# mosfet-drv-for-draft.net
KiCad netlist of a schematic drawn in EAGLE
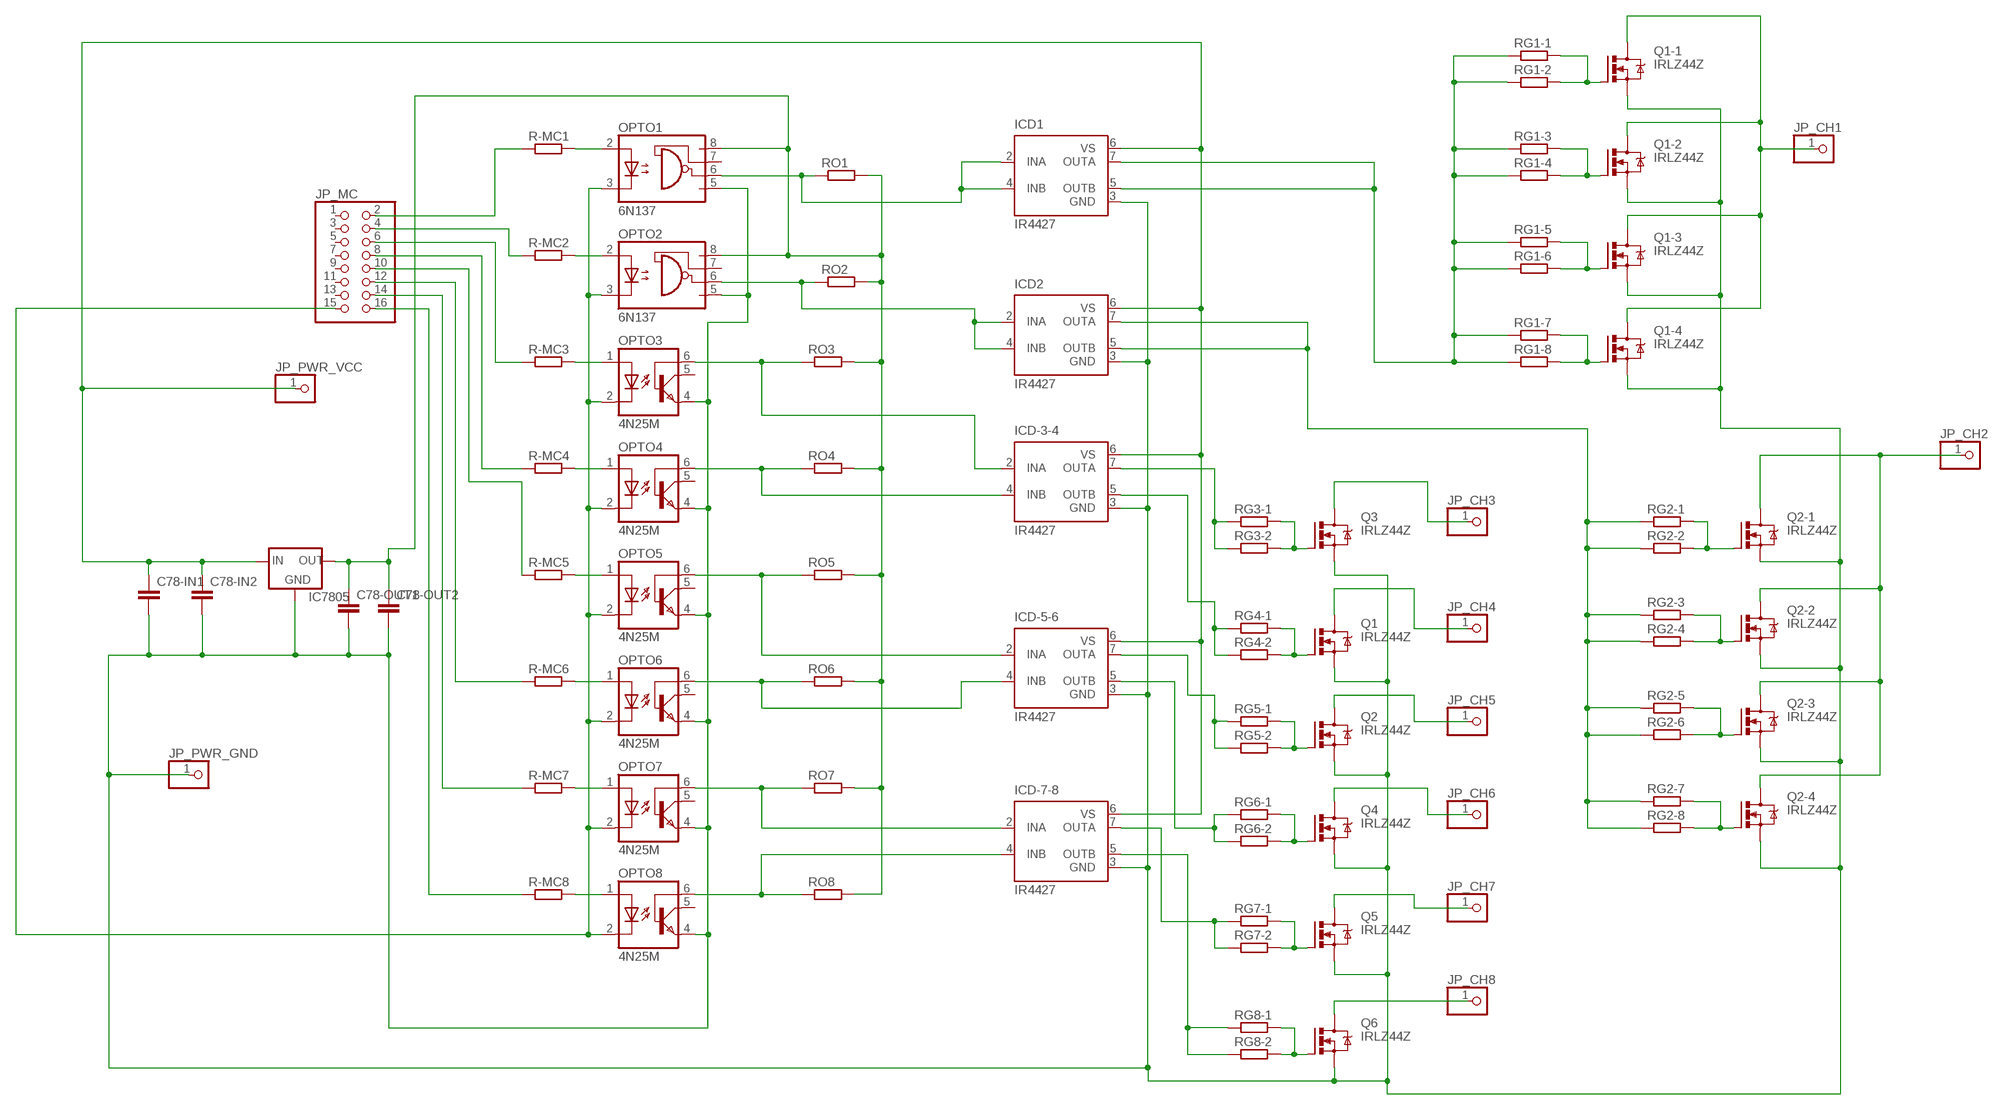
[diagram p0: schematic, sheet 1]

(export (version "E")
  (design (tool "Eeschema 10.0.6"))
  (components
    (comp (ref "C78-IN1")
      (value "C-EU025-060X050")
      (footprint "eagle-import:C025-060X050")
      (libsource (lib "eagle-import") (part "C-EU025-060X050"))
    )
    (comp (ref "C78-IN2")
      (value "C-EU025-060X050")
      (footprint "eagle-import:C025-060X050")
      (libsource (lib "eagle-import") (part "C-EU025-060X050"))
    )
    (comp (ref "C78-OUT1")
      (value "C-EU025-060X050")
      (footprint "eagle-import:C025-060X050")
      (libsource (lib "eagle-import") (part "C-EU025-060X050"))
    )
    (comp (ref "C78-OUT2")
      (value "C-EU025-060X050")
      (footprint "eagle-import:C025-060X050")
      (libsource (lib "eagle-import") (part "C-EU025-060X050"))
    )
    (comp (ref "IC7805")
      (value "78XXS")
      (footprint "eagle-import:78XXS")
      (libsource (lib "eagle-import") (part "78XXS"))
    )
    (comp (ref "ICD-3-4")
      (value "IR4427")
      (footprint "eagle-import:DIL08")
      (fields (field (name "MF") "INTERNATIONAL RECTIFIER(IR)"))
      (libsource (lib "eagle-import") (part "IR4427"))
    )
    (comp (ref "ICD-5-6")
      (value "IR4427")
      (footprint "eagle-import:DIL08")
      (fields (field (name "MF") "INTERNATIONAL RECTIFIER(IR)"))
      (libsource (lib "eagle-import") (part "IR4427"))
    )
    (comp (ref "ICD-7-8")
      (value "IR4427")
      (footprint "eagle-import:DIL08")
      (fields (field (name "MF") "INTERNATIONAL RECTIFIER(IR)"))
      (libsource (lib "eagle-import") (part "IR4427"))
    )
    (comp (ref "ICD1")
      (value "IR4427")
      (footprint "eagle-import:DIL08")
      (fields (field (name "MF") "INTERNATIONAL RECTIFIER(IR)"))
      (libsource (lib "eagle-import") (part "IR4427"))
    )
    (comp (ref "ICD2")
      (value "IR4427")
      (footprint "eagle-import:DIL08")
      (fields (field (name "MF") "INTERNATIONAL RECTIFIER(IR)"))
      (libsource (lib "eagle-import") (part "IR4427"))
    )
    (comp (ref "JP_CH1")
      (value "PINHD-1X1")
      (footprint "eagle-import:1X01")
      (libsource (lib "eagle-import") (part "PINHD-1X1"))
    )
    (comp (ref "JP_CH2")
      (value "PINHD-1X1")
      (footprint "eagle-import:1X01")
      (libsource (lib "eagle-import") (part "PINHD-1X1"))
    )
    (comp (ref "JP_CH3")
      (value "PINHD-1X1")
      (footprint "eagle-import:1X01")
      (libsource (lib "eagle-import") (part "PINHD-1X1"))
    )
    (comp (ref "JP_CH4")
      (value "PINHD-1X1")
      (footprint "eagle-import:1X01")
      (libsource (lib "eagle-import") (part "PINHD-1X1"))
    )
    (comp (ref "JP_CH5")
      (value "PINHD-1X1")
      (footprint "eagle-import:1X01")
      (libsource (lib "eagle-import") (part "PINHD-1X1"))
    )
    (comp (ref "JP_CH6")
      (value "PINHD-1X1")
      (footprint "eagle-import:1X01")
      (libsource (lib "eagle-import") (part "PINHD-1X1"))
    )
    (comp (ref "JP_CH7")
      (value "PINHD-1X1")
      (footprint "eagle-import:1X01")
      (libsource (lib "eagle-import") (part "PINHD-1X1"))
    )
    (comp (ref "JP_CH8")
      (value "PINHD-1X1")
      (footprint "eagle-import:1X01")
      (libsource (lib "eagle-import") (part "PINHD-1X1"))
    )
    (comp (ref "JP_MC")
      (value "PINHD-2X8")
      (footprint "eagle-import:2X08")
      (libsource (lib "eagle-import") (part "PINHD-2X8"))
    )
    (comp (ref "JP_PWR_GND")
      (value "PINHD-1X1")
      (footprint "eagle-import:1X01")
      (libsource (lib "eagle-import") (part "PINHD-1X1"))
    )
    (comp (ref "JP_PWR_VCC")
      (value "PINHD-1X1")
      (footprint "eagle-import:1X01")
      (libsource (lib "eagle-import") (part "PINHD-1X1"))
    )
    (comp (ref "OPTO1")
      (value "6N137")
      (footprint "eagle-import:DIL08")
      (libsource (lib "eagle-import") (part "6N137"))
    )
    (comp (ref "OPTO2")
      (value "6N137")
      (footprint "eagle-import:DIL08")
      (libsource (lib "eagle-import") (part "6N137"))
    )
    (comp (ref "OPTO3")
      (value "4N25M")
      (footprint "eagle-import:DIL06")
      (fields (field (name "MPN") "4N25-M"))
      (libsource (lib "eagle-import") (part "4N?M25"))
    )
    (comp (ref "OPTO4")
      (value "4N25M")
      (footprint "eagle-import:DIL06")
      (fields (field (name "MPN") "4N25-M"))
      (libsource (lib "eagle-import") (part "4N?M25"))
    )
    (comp (ref "OPTO5")
      (value "4N25M")
      (footprint "eagle-import:DIL06")
      (fields (field (name "MPN") "4N25-M"))
      (libsource (lib "eagle-import") (part "4N?M25"))
    )
    (comp (ref "OPTO6")
      (value "4N25M")
      (footprint "eagle-import:DIL06")
      (fields (field (name "MPN") "4N25-M"))
      (libsource (lib "eagle-import") (part "4N?M25"))
    )
    (comp (ref "OPTO7")
      (value "4N25M")
      (footprint "eagle-import:DIL06")
      (fields (field (name "MPN") "4N25-M"))
      (libsource (lib "eagle-import") (part "4N?M25"))
    )
    (comp (ref "OPTO8")
      (value "4N25M")
      (footprint "eagle-import:DIL06")
      (fields (field (name "MPN") "4N25-M"))
      (libsource (lib "eagle-import") (part "4N?M25"))
    )
    (comp (ref "Q1")
      (value "IRLZ44Z")
      (footprint "eagle-import:TO220BH")
      (libsource (lib "eagle-import") (part "IRLZ44Z"))
    )
    (comp (ref "Q1-1")
      (value "IRLZ44Z")
      (footprint "eagle-import:TO220BH")
      (libsource (lib "eagle-import") (part "IRLZ44Z"))
    )
    (comp (ref "Q1-2")
      (value "IRLZ44Z")
      (footprint "eagle-import:TO220BH")
      (libsource (lib "eagle-import") (part "IRLZ44Z"))
    )
    (comp (ref "Q1-3")
      (value "IRLZ44Z")
      (footprint "eagle-import:TO220BH")
      (libsource (lib "eagle-import") (part "IRLZ44Z"))
    )
    (comp (ref "Q1-4")
      (value "IRLZ44Z")
      (footprint "eagle-import:TO220BH")
      (libsource (lib "eagle-import") (part "IRLZ44Z"))
    )
    (comp (ref "Q2")
      (value "IRLZ44Z")
      (footprint "eagle-import:TO220BH")
      (libsource (lib "eagle-import") (part "IRLZ44Z"))
    )
    (comp (ref "Q2-1")
      (value "IRLZ44Z")
      (footprint "eagle-import:TO220BH")
      (libsource (lib "eagle-import") (part "IRLZ44Z"))
    )
    (comp (ref "Q2-2")
      (value "IRLZ44Z")
      (footprint "eagle-import:TO220BH")
      (libsource (lib "eagle-import") (part "IRLZ44Z"))
    )
    (comp (ref "Q2-3")
      (value "IRLZ44Z")
      (footprint "eagle-import:TO220BH")
      (libsource (lib "eagle-import") (part "IRLZ44Z"))
    )
    (comp (ref "Q2-4")
      (value "IRLZ44Z")
      (footprint "eagle-import:TO220BH")
      (libsource (lib "eagle-import") (part "IRLZ44Z"))
    )
    (comp (ref "Q3")
      (value "IRLZ44Z")
      (footprint "eagle-import:TO220BH")
      (libsource (lib "eagle-import") (part "IRLZ44Z"))
    )
    (comp (ref "Q4")
      (value "IRLZ44Z")
      (footprint "eagle-import:TO220BH")
      (libsource (lib "eagle-import") (part "IRLZ44Z"))
    )
    (comp (ref "Q5")
      (value "IRLZ44Z")
      (footprint "eagle-import:TO220BH")
      (libsource (lib "eagle-import") (part "IRLZ44Z"))
    )
    (comp (ref "Q6")
      (value "IRLZ44Z")
      (footprint "eagle-import:TO220BH")
      (libsource (lib "eagle-import") (part "IRLZ44Z"))
    )
    (comp (ref "R-MC1")
      (value "R-EU_M1206")
      (footprint "eagle-import:M1206")
      (libsource (lib "eagle-import") (part "R-EU_M1206"))
    )
    (comp (ref "R-MC2")
      (value "R-EU_M1206")
      (footprint "eagle-import:M1206")
      (libsource (lib "eagle-import") (part "R-EU_M1206"))
    )
    (comp (ref "R-MC3")
      (value "R-EU_M1206")
      (footprint "eagle-import:M1206")
      (libsource (lib "eagle-import") (part "R-EU_M1206"))
    )
    (comp (ref "R-MC4")
      (value "R-EU_M1206")
      (footprint "eagle-import:M1206")
      (libsource (lib "eagle-import") (part "R-EU_M1206"))
    )
    (comp (ref "R-MC5")
      (value "R-EU_M1206")
      (footprint "eagle-import:M1206")
      (libsource (lib "eagle-import") (part "R-EU_M1206"))
    )
    (comp (ref "R-MC6")
      (value "R-EU_M1206")
      (footprint "eagle-import:M1206")
      (libsource (lib "eagle-import") (part "R-EU_M1206"))
    )
    (comp (ref "R-MC7")
      (value "R-EU_M1206")
      (footprint "eagle-import:M1206")
      (libsource (lib "eagle-import") (part "R-EU_M1206"))
    )
    (comp (ref "R-MC8")
      (value "R-EU_M1206")
      (footprint "eagle-import:M1206")
      (libsource (lib "eagle-import") (part "R-EU_M1206"))
    )
    (comp (ref "RG1-1")
      (value "R-EU_0207/15")
      (footprint "eagle-import:0207_15")
      (libsource (lib "eagle-import") (part "R-EU_0207/15"))
    )
    (comp (ref "RG1-2")
      (value "R-EU_0207/15")
      (footprint "eagle-import:0207_15")
      (libsource (lib "eagle-import") (part "R-EU_0207/15"))
    )
    (comp (ref "RG1-3")
      (value "R-EU_0207/15")
      (footprint "eagle-import:0207_15")
      (libsource (lib "eagle-import") (part "R-EU_0207/15"))
    )
    (comp (ref "RG1-4")
      (value "R-EU_0207/15")
      (footprint "eagle-import:0207_15")
      (libsource (lib "eagle-import") (part "R-EU_0207/15"))
    )
    (comp (ref "RG1-5")
      (value "R-EU_0207/15")
      (footprint "eagle-import:0207_15")
      (libsource (lib "eagle-import") (part "R-EU_0207/15"))
    )
    (comp (ref "RG1-6")
      (value "R-EU_0207/15")
      (footprint "eagle-import:0207_15")
      (libsource (lib "eagle-import") (part "R-EU_0207/15"))
    )
    (comp (ref "RG1-7")
      (value "R-EU_0207/15")
      (footprint "eagle-import:0207_15")
      (libsource (lib "eagle-import") (part "R-EU_0207/15"))
    )
    (comp (ref "RG1-8")
      (value "R-EU_0207/15")
      (footprint "eagle-import:0207_15")
      (libsource (lib "eagle-import") (part "R-EU_0207/15"))
    )
    (comp (ref "RG2-1")
      (value "R-EU_0207/15")
      (footprint "eagle-import:0207_15")
      (libsource (lib "eagle-import") (part "R-EU_0207/15"))
    )
    (comp (ref "RG2-2")
      (value "R-EU_0207/15")
      (footprint "eagle-import:0207_15")
      (libsource (lib "eagle-import") (part "R-EU_0207/15"))
    )
    (comp (ref "RG2-3")
      (value "R-EU_0207/15")
      (footprint "eagle-import:0207_15")
      (libsource (lib "eagle-import") (part "R-EU_0207/15"))
    )
    (comp (ref "RG2-4")
      (value "R-EU_0207/15")
      (footprint "eagle-import:0207_15")
      (libsource (lib "eagle-import") (part "R-EU_0207/15"))
    )
    (comp (ref "RG2-5")
      (value "R-EU_0207/15")
      (footprint "eagle-import:0207_15")
      (libsource (lib "eagle-import") (part "R-EU_0207/15"))
    )
    (comp (ref "RG2-6")
      (value "R-EU_0207/15")
      (footprint "eagle-import:0207_15")
      (libsource (lib "eagle-import") (part "R-EU_0207/15"))
    )
    (comp (ref "RG2-7")
      (value "R-EU_0207/15")
      (footprint "eagle-import:0207_15")
      (libsource (lib "eagle-import") (part "R-EU_0207/15"))
    )
    (comp (ref "RG2-8")
      (value "R-EU_0207/15")
      (footprint "eagle-import:0207_15")
      (libsource (lib "eagle-import") (part "R-EU_0207/15"))
    )
    (comp (ref "RG3-1")
      (value "R-EU_0207/15")
      (footprint "eagle-import:0207_15")
      (libsource (lib "eagle-import") (part "R-EU_0207/15"))
    )
    (comp (ref "RG3-2")
      (value "R-EU_0207/15")
      (footprint "eagle-import:0207_15")
      (libsource (lib "eagle-import") (part "R-EU_0207/15"))
    )
    (comp (ref "RG4-1")
      (value "R-EU_0207/15")
      (footprint "eagle-import:0207_15")
      (libsource (lib "eagle-import") (part "R-EU_0207/15"))
    )
    (comp (ref "RG4-2")
      (value "R-EU_0207/15")
      (footprint "eagle-import:0207_15")
      (libsource (lib "eagle-import") (part "R-EU_0207/15"))
    )
    (comp (ref "RG5-1")
      (value "R-EU_0207/15")
      (footprint "eagle-import:0207_15")
      (libsource (lib "eagle-import") (part "R-EU_0207/15"))
    )
    (comp (ref "RG5-2")
      (value "R-EU_0207/15")
      (footprint "eagle-import:0207_15")
      (libsource (lib "eagle-import") (part "R-EU_0207/15"))
    )
    (comp (ref "RG6-1")
      (value "R-EU_0207/15")
      (footprint "eagle-import:0207_15")
      (libsource (lib "eagle-import") (part "R-EU_0207/15"))
    )
    (comp (ref "RG6-2")
      (value "R-EU_0207/15")
      (footprint "eagle-import:0207_15")
      (libsource (lib "eagle-import") (part "R-EU_0207/15"))
    )
    (comp (ref "RG7-1")
      (value "R-EU_0207/15")
      (footprint "eagle-import:0207_15")
      (libsource (lib "eagle-import") (part "R-EU_0207/15"))
    )
    (comp (ref "RG7-2")
      (value "R-EU_0207/15")
      (footprint "eagle-import:0207_15")
      (libsource (lib "eagle-import") (part "R-EU_0207/15"))
    )
    (comp (ref "RG8-1")
      (value "R-EU_0207/15")
      (footprint "eagle-import:0207_15")
      (libsource (lib "eagle-import") (part "R-EU_0207/15"))
    )
    (comp (ref "RG8-2")
      (value "R-EU_0207/15")
      (footprint "eagle-import:0207_15")
      (libsource (lib "eagle-import") (part "R-EU_0207/15"))
    )
    (comp (ref "RO1")
      (value "R-EU_M1206")
      (footprint "eagle-import:M1206")
      (libsource (lib "eagle-import") (part "R-EU_M1206"))
    )
    (comp (ref "RO2")
      (value "R-EU_M1206")
      (footprint "eagle-import:M1206")
      (libsource (lib "eagle-import") (part "R-EU_M1206"))
    )
    (comp (ref "RO3")
      (value "R-EU_M1206")
      (footprint "eagle-import:M1206")
      (libsource (lib "eagle-import") (part "R-EU_M1206"))
    )
    (comp (ref "RO4")
      (value "R-EU_M1206")
      (footprint "eagle-import:M1206")
      (libsource (lib "eagle-import") (part "R-EU_M1206"))
    )
    (comp (ref "RO5")
      (value "R-EU_M1206")
      (footprint "eagle-import:M1206")
      (libsource (lib "eagle-import") (part "R-EU_M1206"))
    )
    (comp (ref "RO6")
      (value "R-EU_M1206")
      (footprint "eagle-import:M1206")
      (libsource (lib "eagle-import") (part "R-EU_M1206"))
    )
    (comp (ref "RO7")
      (value "R-EU_M1206")
      (footprint "eagle-import:M1206")
      (libsource (lib "eagle-import") (part "R-EU_M1206"))
    )
    (comp (ref "RO8")
      (value "R-EU_M1206")
      (footprint "eagle-import:M1206")
      (libsource (lib "eagle-import") (part "R-EU_M1206"))
    )
  )
  (nets
    (net (code "1") (name "Net-(ICD-3-4-GND)") (class "Default")
      (node (ref "C78-IN1") (pin "2") (pinfunction "2_2") (pintype "passive"))
      (node (ref "C78-IN2") (pin "2") (pinfunction "2_2") (pintype "passive"))
      (node (ref "C78-OUT1") (pin "2") (pinfunction "2_2") (pintype "passive"))
      (node (ref "C78-OUT2") (pin "2") (pinfunction "2_2") (pintype "passive"))
      (node (ref "IC7805") (pin "GND") (pinfunction "GND_GND") (pintype "input"))
      (node (ref "ICD-3-4") (pin "3") (pinfunction "GND_3") (pintype "power_in"))
      (node (ref "ICD-5-6") (pin "3") (pinfunction "GND_3") (pintype "power_in"))
      (node (ref "ICD-7-8") (pin "3") (pinfunction "GND_3") (pintype "power_in"))
      (node (ref "ICD1") (pin "3") (pinfunction "GND_3") (pintype "power_in"))
      (node (ref "ICD2") (pin "3") (pinfunction "GND_3") (pintype "power_in"))
      (node (ref "JP_PWR_GND") (pin "1") (pinfunction "1_1") (pintype "passive"))
      (node (ref "OPTO1") (pin "5") (pinfunction "GND_5") (pintype "passive"))
      (node (ref "OPTO2") (pin "5") (pinfunction "GND_5") (pintype "passive"))
      (node (ref "OPTO3") (pin "4") (pinfunction "EMI_4") (pintype "passive"))
      (node (ref "OPTO4") (pin "4") (pinfunction "EMI_4") (pintype "passive"))
      (node (ref "OPTO5") (pin "4") (pinfunction "EMI_4") (pintype "passive"))
      (node (ref "OPTO6") (pin "4") (pinfunction "EMI_4") (pintype "passive"))
      (node (ref "OPTO7") (pin "4") (pinfunction "EMI_4") (pintype "passive"))
      (node (ref "OPTO8") (pin "4") (pinfunction "EMI_4") (pintype "passive"))
      (node (ref "Q1") (pin "S") (pinfunction "S_S") (pintype "passive"))
      (node (ref "Q1-1") (pin "S") (pinfunction "S_S") (pintype "passive"))
      (node (ref "Q1-2") (pin "S") (pinfunction "S_S") (pintype "passive"))
      (node (ref "Q1-3") (pin "S") (pinfunction "S_S") (pintype "passive"))
      (node (ref "Q1-4") (pin "S") (pinfunction "S_S") (pintype "passive"))
      (node (ref "Q2") (pin "S") (pinfunction "S_S") (pintype "passive"))
      (node (ref "Q2-1") (pin "S") (pinfunction "S_S") (pintype "passive"))
      (node (ref "Q2-2") (pin "S") (pinfunction "S_S") (pintype "passive"))
      (node (ref "Q2-3") (pin "S") (pinfunction "S_S") (pintype "passive"))
      (node (ref "Q2-4") (pin "S") (pinfunction "S_S") (pintype "passive"))
      (node (ref "Q3") (pin "S") (pinfunction "S_S") (pintype "passive"))
      (node (ref "Q4") (pin "S") (pinfunction "S_S") (pintype "passive"))
      (node (ref "Q5") (pin "S") (pinfunction "S_S") (pintype "passive"))
      (node (ref "Q6") (pin "S") (pinfunction "S_S") (pintype "passive"))
    )
    (net (code "2") (name "Net-(ICD-3-4-INA)") (class "Default")
      (node (ref "ICD-3-4") (pin "2") (pinfunction "INA_2") (pintype "input"))
      (node (ref "OPTO3") (pin "6") (pinfunction "BAS_6") (pintype "passive"))
      (node (ref "RO3") (pin "1") (pinfunction "1_1") (pintype "passive"))
    )
    (net (code "3") (name "Net-(ICD-3-4-INB)") (class "Default")
      (node (ref "ICD-3-4") (pin "4") (pinfunction "INB_4") (pintype "input"))
      (node (ref "OPTO4") (pin "6") (pinfunction "BAS_6") (pintype "passive"))
      (node (ref "RO4") (pin "1") (pinfunction "1_1") (pintype "passive"))
    )
    (net (code "4") (name "Net-(ICD-3-4-OUTA)") (class "Default")
      (node (ref "ICD-3-4") (pin "7") (pinfunction "OUTA_7") (pintype "output"))
      (node (ref "RG3-1") (pin "1") (pinfunction "1_1") (pintype "passive"))
      (node (ref "RG3-2") (pin "1") (pinfunction "1_1") (pintype "passive"))
    )
    (net (code "5") (name "Net-(ICD-3-4-OUTB)") (class "Default")
      (node (ref "ICD-3-4") (pin "5") (pinfunction "OUTB_5") (pintype "output"))
      (node (ref "RG4-1") (pin "1") (pinfunction "1_1") (pintype "passive"))
      (node (ref "RG4-2") (pin "1") (pinfunction "1_1") (pintype "passive"))
    )
    (net (code "6") (name "Net-(ICD-3-4-VS)") (class "Default")
      (node (ref "C78-IN1") (pin "1") (pinfunction "1_1") (pintype "passive"))
      (node (ref "C78-IN2") (pin "1") (pinfunction "1_1") (pintype "passive"))
      (node (ref "IC7805") (pin "IN") (pinfunction "IN_IN") (pintype "input"))
      (node (ref "ICD-3-4") (pin "6") (pinfunction "VS_6") (pintype "power_in"))
      (node (ref "ICD-5-6") (pin "6") (pinfunction "VS_6") (pintype "power_in"))
      (node (ref "ICD-7-8") (pin "6") (pinfunction "VS_6") (pintype "power_in"))
      (node (ref "ICD1") (pin "6") (pinfunction "VS_6") (pintype "power_in"))
      (node (ref "ICD2") (pin "6") (pinfunction "VS_6") (pintype "power_in"))
      (node (ref "JP_PWR_VCC") (pin "1") (pinfunction "1_1") (pintype "passive"))
    )
    (net (code "7") (name "Net-(ICD-5-6-INA)") (class "Default")
      (node (ref "ICD-5-6") (pin "2") (pinfunction "INA_2") (pintype "input"))
      (node (ref "OPTO5") (pin "6") (pinfunction "BAS_6") (pintype "passive"))
      (node (ref "RO5") (pin "1") (pinfunction "1_1") (pintype "passive"))
    )
    (net (code "8") (name "Net-(ICD-5-6-INB)") (class "Default")
      (node (ref "ICD-5-6") (pin "4") (pinfunction "INB_4") (pintype "input"))
      (node (ref "OPTO6") (pin "6") (pinfunction "BAS_6") (pintype "passive"))
      (node (ref "RO6") (pin "1") (pinfunction "1_1") (pintype "passive"))
    )
    (net (code "9") (name "Net-(ICD-5-6-OUTA)") (class "Default")
      (node (ref "ICD-5-6") (pin "7") (pinfunction "OUTA_7") (pintype "output"))
      (node (ref "RG5-1") (pin "1") (pinfunction "1_1") (pintype "passive"))
      (node (ref "RG5-2") (pin "1") (pinfunction "1_1") (pintype "passive"))
    )
    (net (code "10") (name "Net-(ICD-5-6-OUTB)") (class "Default")
      (node (ref "ICD-5-6") (pin "5") (pinfunction "OUTB_5") (pintype "output"))
      (node (ref "RG6-1") (pin "1") (pinfunction "1_1") (pintype "passive"))
      (node (ref "RG6-2") (pin "1") (pinfunction "1_1") (pintype "passive"))
    )
    (net (code "11") (name "Net-(ICD-7-8-INA)") (class "Default")
      (node (ref "ICD-7-8") (pin "2") (pinfunction "INA_2") (pintype "input"))
      (node (ref "OPTO7") (pin "6") (pinfunction "BAS_6") (pintype "passive"))
      (node (ref "RO7") (pin "1") (pinfunction "1_1") (pintype "passive"))
    )
    (net (code "12") (name "Net-(ICD-7-8-INB)") (class "Default")
      (node (ref "ICD-7-8") (pin "4") (pinfunction "INB_4") (pintype "input"))
      (node (ref "OPTO8") (pin "6") (pinfunction "BAS_6") (pintype "passive"))
      (node (ref "RO8") (pin "1") (pinfunction "1_1") (pintype "passive"))
    )
    (net (code "13") (name "Net-(ICD-7-8-OUTA)") (class "Default")
      (node (ref "ICD-7-8") (pin "7") (pinfunction "OUTA_7") (pintype "output"))
      (node (ref "RG7-1") (pin "1") (pinfunction "1_1") (pintype "passive"))
      (node (ref "RG7-2") (pin "1") (pinfunction "1_1") (pintype "passive"))
    )
    (net (code "14") (name "Net-(ICD-7-8-OUTB)") (class "Default")
      (node (ref "ICD-7-8") (pin "5") (pinfunction "OUTB_5") (pintype "output"))
      (node (ref "RG8-1") (pin "1") (pinfunction "1_1") (pintype "passive"))
      (node (ref "RG8-2") (pin "1") (pinfunction "1_1") (pintype "passive"))
    )
    (net (code "15") (name "Net-(ICD1-INA)") (class "Default")
      (node (ref "ICD1") (pin "2") (pinfunction "INA_2") (pintype "input"))
      (node (ref "ICD1") (pin "4") (pinfunction "INB_4") (pintype "input"))
      (node (ref "OPTO1") (pin "6") (pinfunction "VO_6") (pintype "passive"))
      (node (ref "RO1") (pin "1") (pinfunction "1_1") (pintype "passive"))
    )
    (net (code "16") (name "Net-(ICD1-OUTA)") (class "Default")
      (node (ref "ICD1") (pin "5") (pinfunction "OUTB_5") (pintype "output"))
      (node (ref "ICD1") (pin "7") (pinfunction "OUTA_7") (pintype "output"))
      (node (ref "RG1-1") (pin "1") (pinfunction "1_1") (pintype "passive"))
      (node (ref "RG1-2") (pin "1") (pinfunction "1_1") (pintype "passive"))
      (node (ref "RG1-3") (pin "1") (pinfunction "1_1") (pintype "passive"))
      (node (ref "RG1-4") (pin "1") (pinfunction "1_1") (pintype "passive"))
      (node (ref "RG1-5") (pin "1") (pinfunction "1_1") (pintype "passive"))
      (node (ref "RG1-6") (pin "1") (pinfunction "1_1") (pintype "passive"))
      (node (ref "RG1-7") (pin "1") (pinfunction "1_1") (pintype "passive"))
      (node (ref "RG1-8") (pin "1") (pinfunction "1_1") (pintype "passive"))
    )
    (net (code "17") (name "Net-(ICD2-INA)") (class "Default")
      (node (ref "ICD2") (pin "2") (pinfunction "INA_2") (pintype "input"))
      (node (ref "ICD2") (pin "4") (pinfunction "INB_4") (pintype "input"))
      (node (ref "OPTO2") (pin "6") (pinfunction "VO_6") (pintype "passive"))
      (node (ref "RO2") (pin "1") (pinfunction "1_1") (pintype "passive"))
    )
    (net (code "18") (name "Net-(ICD2-OUTA)") (class "Default")
      (node (ref "ICD2") (pin "5") (pinfunction "OUTB_5") (pintype "output"))
      (node (ref "ICD2") (pin "7") (pinfunction "OUTA_7") (pintype "output"))
      (node (ref "RG2-1") (pin "1") (pinfunction "1_1") (pintype "passive"))
      (node (ref "RG2-2") (pin "1") (pinfunction "1_1") (pintype "passive"))
      (node (ref "RG2-3") (pin "1") (pinfunction "1_1") (pintype "passive"))
      (node (ref "RG2-4") (pin "1") (pinfunction "1_1") (pintype "passive"))
      (node (ref "RG2-5") (pin "1") (pinfunction "1_1") (pintype "passive"))
      (node (ref "RG2-6") (pin "1") (pinfunction "1_1") (pintype "passive"))
      (node (ref "RG2-7") (pin "1") (pinfunction "1_1") (pintype "passive"))
      (node (ref "RG2-8") (pin "1") (pinfunction "1_1") (pintype "passive"))
    )
    (net (code "19") (name "Net-(JP_CH1-Pad1)") (class "Default")
      (node (ref "JP_CH1") (pin "1") (pinfunction "1_1") (pintype "passive"))
      (node (ref "Q1-1") (pin "D") (pinfunction "D_D") (pintype "passive"))
      (node (ref "Q1-2") (pin "D") (pinfunction "D_D") (pintype "passive"))
      (node (ref "Q1-3") (pin "D") (pinfunction "D_D") (pintype "passive"))
      (node (ref "Q1-4") (pin "D") (pinfunction "D_D") (pintype "passive"))
    )
    (net (code "20") (name "Net-(JP_CH2-Pad1)") (class "Default")
      (node (ref "JP_CH2") (pin "1") (pinfunction "1_1") (pintype "passive"))
      (node (ref "Q2-1") (pin "D") (pinfunction "D_D") (pintype "passive"))
      (node (ref "Q2-2") (pin "D") (pinfunction "D_D") (pintype "passive"))
      (node (ref "Q2-3") (pin "D") (pinfunction "D_D") (pintype "passive"))
      (node (ref "Q2-4") (pin "D") (pinfunction "D_D") (pintype "passive"))
    )
    (net (code "21") (name "Net-(JP_CH3-Pad1)") (class "Default")
      (node (ref "JP_CH3") (pin "1") (pinfunction "1_1") (pintype "passive"))
      (node (ref "Q3") (pin "D") (pinfunction "D_D") (pintype "passive"))
    )
    (net (code "22") (name "Net-(JP_CH4-Pad1)") (class "Default")
      (node (ref "JP_CH4") (pin "1") (pinfunction "1_1") (pintype "passive"))
      (node (ref "Q1") (pin "D") (pinfunction "D_D") (pintype "passive"))
    )
    (net (code "23") (name "Net-(JP_CH5-Pad1)") (class "Default")
      (node (ref "JP_CH5") (pin "1") (pinfunction "1_1") (pintype "passive"))
      (node (ref "Q2") (pin "D") (pinfunction "D_D") (pintype "passive"))
    )
    (net (code "24") (name "Net-(JP_CH6-Pad1)") (class "Default")
      (node (ref "JP_CH6") (pin "1") (pinfunction "1_1") (pintype "passive"))
      (node (ref "Q4") (pin "D") (pinfunction "D_D") (pintype "passive"))
    )
    (net (code "25") (name "Net-(JP_CH7-Pad1)") (class "Default")
      (node (ref "JP_CH7") (pin "1") (pinfunction "1_1") (pintype "passive"))
      (node (ref "Q5") (pin "D") (pinfunction "D_D") (pintype "passive"))
    )
    (net (code "26") (name "Net-(JP_CH8-Pad1)") (class "Default")
      (node (ref "JP_CH8") (pin "1") (pinfunction "1_1") (pintype "passive"))
      (node (ref "Q6") (pin "D") (pinfunction "D_D") (pintype "passive"))
    )
    (net (code "27") (name "Net-(JP_MC-Pad2)") (class "Default")
      (node (ref "JP_MC") (pin "2") (pinfunction "2_2") (pintype "passive"))
      (node (ref "R-MC1") (pin "1") (pinfunction "1_1") (pintype "passive"))
    )
    (net (code "28") (name "Net-(JP_MC-Pad4)") (class "Default")
      (node (ref "JP_MC") (pin "4") (pinfunction "4_4") (pintype "passive"))
      (node (ref "R-MC2") (pin "1") (pinfunction "1_1") (pintype "passive"))
    )
    (net (code "29") (name "Net-(JP_MC-Pad6)") (class "Default")
      (node (ref "JP_MC") (pin "6") (pinfunction "6_6") (pintype "passive"))
      (node (ref "R-MC3") (pin "1") (pinfunction "1_1") (pintype "passive"))
    )
    (net (code "30") (name "Net-(JP_MC-Pad8)") (class "Default")
      (node (ref "JP_MC") (pin "8") (pinfunction "8_8") (pintype "passive"))
      (node (ref "R-MC4") (pin "1") (pinfunction "1_1") (pintype "passive"))
    )
    (net (code "31") (name "Net-(JP_MC-Pad10)") (class "Default")
      (node (ref "JP_MC") (pin "10") (pinfunction "10_10") (pintype "passive"))
      (node (ref "R-MC5") (pin "1") (pinfunction "1_1") (pintype "passive"))
    )
    (net (code "32") (name "Net-(JP_MC-Pad12)") (class "Default")
      (node (ref "JP_MC") (pin "12") (pinfunction "12_12") (pintype "passive"))
      (node (ref "R-MC6") (pin "1") (pinfunction "1_1") (pintype "passive"))
    )
    (net (code "33") (name "Net-(JP_MC-Pad14)") (class "Default")
      (node (ref "JP_MC") (pin "14") (pinfunction "14_14") (pintype "passive"))
      (node (ref "R-MC7") (pin "1") (pinfunction "1_1") (pintype "passive"))
    )
    (net (code "34") (name "Net-(JP_MC-Pad16)") (class "Default")
      (node (ref "JP_MC") (pin "16") (pinfunction "16_16") (pintype "passive"))
      (node (ref "R-MC8") (pin "1") (pinfunction "1_1") (pintype "passive"))
    )
    (net (code "35") (name "Net-(OPTO1-A)") (class "Default")
      (node (ref "OPTO1") (pin "2") (pinfunction "A_2") (pintype "passive"))
      (node (ref "R-MC1") (pin "2") (pinfunction "2_2") (pintype "passive"))
    )
    (net (code "36") (name "Net-(OPTO1-C)") (class "Default")
      (node (ref "JP_MC") (pin "15") (pinfunction "15_15") (pintype "passive"))
      (node (ref "OPTO1") (pin "3") (pinfunction "C_3") (pintype "passive"))
      (node (ref "OPTO2") (pin "3") (pinfunction "C_3") (pintype "passive"))
      (node (ref "OPTO3") (pin "2") (pinfunction "C_2") (pintype "passive"))
      (node (ref "OPTO4") (pin "2") (pinfunction "C_2") (pintype "passive"))
      (node (ref "OPTO5") (pin "2") (pinfunction "C_2") (pintype "passive"))
      (node (ref "OPTO6") (pin "2") (pinfunction "C_2") (pintype "passive"))
      (node (ref "OPTO7") (pin "2") (pinfunction "C_2") (pintype "passive"))
      (node (ref "OPTO8") (pin "2") (pinfunction "C_2") (pintype "passive"))
    )
    (net (code "37") (name "Net-(OPTO1-VCC)") (class "Default")
      (node (ref "C78-OUT1") (pin "1") (pinfunction "1_1") (pintype "passive"))
      (node (ref "C78-OUT2") (pin "1") (pinfunction "1_1") (pintype "passive"))
      (node (ref "IC7805") (pin "OUT") (pinfunction "OUT_OUT") (pintype "passive"))
      (node (ref "OPTO1") (pin "8") (pinfunction "VCC_8") (pintype "passive"))
      (node (ref "OPTO2") (pin "8") (pinfunction "VCC_8") (pintype "passive"))
      (node (ref "RO1") (pin "2") (pinfunction "2_2") (pintype "passive"))
      (node (ref "RO2") (pin "2") (pinfunction "2_2") (pintype "passive"))
      (node (ref "RO3") (pin "2") (pinfunction "2_2") (pintype "passive"))
      (node (ref "RO4") (pin "2") (pinfunction "2_2") (pintype "passive"))
      (node (ref "RO5") (pin "2") (pinfunction "2_2") (pintype "passive"))
      (node (ref "RO6") (pin "2") (pinfunction "2_2") (pintype "passive"))
      (node (ref "RO7") (pin "2") (pinfunction "2_2") (pintype "passive"))
      (node (ref "RO8") (pin "2") (pinfunction "2_2") (pintype "passive"))
    )
    (net (code "38") (name "Net-(OPTO2-A)") (class "Default")
      (node (ref "OPTO2") (pin "2") (pinfunction "A_2") (pintype "passive"))
      (node (ref "R-MC2") (pin "2") (pinfunction "2_2") (pintype "passive"))
    )
    (net (code "39") (name "Net-(OPTO3-A)") (class "Default")
      (node (ref "OPTO3") (pin "1") (pinfunction "A_1") (pintype "passive"))
      (node (ref "R-MC3") (pin "2") (pinfunction "2_2") (pintype "passive"))
    )
    (net (code "40") (name "Net-(OPTO4-A)") (class "Default")
      (node (ref "OPTO4") (pin "1") (pinfunction "A_1") (pintype "passive"))
      (node (ref "R-MC4") (pin "2") (pinfunction "2_2") (pintype "passive"))
    )
    (net (code "41") (name "Net-(OPTO5-A)") (class "Default")
      (node (ref "OPTO5") (pin "1") (pinfunction "A_1") (pintype "passive"))
      (node (ref "R-MC5") (pin "2") (pinfunction "2_2") (pintype "passive"))
    )
    (net (code "42") (name "Net-(OPTO6-A)") (class "Default")
      (node (ref "OPTO6") (pin "1") (pinfunction "A_1") (pintype "passive"))
      (node (ref "R-MC6") (pin "2") (pinfunction "2_2") (pintype "passive"))
    )
    (net (code "43") (name "Net-(OPTO7-A)") (class "Default")
      (node (ref "OPTO7") (pin "1") (pinfunction "A_1") (pintype "passive"))
      (node (ref "R-MC7") (pin "2") (pinfunction "2_2") (pintype "passive"))
    )
    (net (code "44") (name "Net-(OPTO8-A)") (class "Default")
      (node (ref "OPTO8") (pin "1") (pinfunction "A_1") (pintype "passive"))
      (node (ref "R-MC8") (pin "2") (pinfunction "2_2") (pintype "passive"))
    )
    (net (code "45") (name "Net-(Q1-1-PadG)") (class "Default")
      (node (ref "Q1-1") (pin "G") (pinfunction "G_G") (pintype "passive"))
      (node (ref "RG1-1") (pin "2") (pinfunction "2_2") (pintype "passive"))
      (node (ref "RG1-2") (pin "2") (pinfunction "2_2") (pintype "passive"))
    )
    (net (code "46") (name "Net-(Q1-2-PadG)") (class "Default")
      (node (ref "Q1-2") (pin "G") (pinfunction "G_G") (pintype "passive"))
      (node (ref "RG1-3") (pin "2") (pinfunction "2_2") (pintype "passive"))
      (node (ref "RG1-4") (pin "2") (pinfunction "2_2") (pintype "passive"))
    )
    (net (code "47") (name "Net-(Q1-3-PadG)") (class "Default")
      (node (ref "Q1-3") (pin "G") (pinfunction "G_G") (pintype "passive"))
      (node (ref "RG1-5") (pin "2") (pinfunction "2_2") (pintype "passive"))
      (node (ref "RG1-6") (pin "2") (pinfunction "2_2") (pintype "passive"))
    )
    (net (code "48") (name "Net-(Q1-4-PadG)") (class "Default")
      (node (ref "Q1-4") (pin "G") (pinfunction "G_G") (pintype "passive"))
      (node (ref "RG1-7") (pin "2") (pinfunction "2_2") (pintype "passive"))
      (node (ref "RG1-8") (pin "2") (pinfunction "2_2") (pintype "passive"))
    )
    (net (code "49") (name "Net-(Q1-PadG)") (class "Default")
      (node (ref "Q1") (pin "G") (pinfunction "G_G") (pintype "passive"))
      (node (ref "RG4-1") (pin "2") (pinfunction "2_2") (pintype "passive"))
      (node (ref "RG4-2") (pin "2") (pinfunction "2_2") (pintype "passive"))
    )
    (net (code "50") (name "Net-(Q2-1-PadG)") (class "Default")
      (node (ref "Q2-1") (pin "G") (pinfunction "G_G") (pintype "passive"))
      (node (ref "RG2-1") (pin "2") (pinfunction "2_2") (pintype "passive"))
      (node (ref "RG2-2") (pin "2") (pinfunction "2_2") (pintype "passive"))
    )
    (net (code "51") (name "Net-(Q2-2-PadG)") (class "Default")
      (node (ref "Q2-2") (pin "G") (pinfunction "G_G") (pintype "passive"))
      (node (ref "RG2-3") (pin "2") (pinfunction "2_2") (pintype "passive"))
      (node (ref "RG2-4") (pin "2") (pinfunction "2_2") (pintype "passive"))
    )
    (net (code "52") (name "Net-(Q2-3-PadG)") (class "Default")
      (node (ref "Q2-3") (pin "G") (pinfunction "G_G") (pintype "passive"))
      (node (ref "RG2-5") (pin "2") (pinfunction "2_2") (pintype "passive"))
      (node (ref "RG2-6") (pin "2") (pinfunction "2_2") (pintype "passive"))
    )
    (net (code "53") (name "Net-(Q2-4-PadG)") (class "Default")
      (node (ref "Q2-4") (pin "G") (pinfunction "G_G") (pintype "passive"))
      (node (ref "RG2-7") (pin "2") (pinfunction "2_2") (pintype "passive"))
      (node (ref "RG2-8") (pin "2") (pinfunction "2_2") (pintype "passive"))
    )
    (net (code "54") (name "Net-(Q2-PadG)") (class "Default")
      (node (ref "Q2") (pin "G") (pinfunction "G_G") (pintype "passive"))
      (node (ref "RG5-1") (pin "2") (pinfunction "2_2") (pintype "passive"))
      (node (ref "RG5-2") (pin "2") (pinfunction "2_2") (pintype "passive"))
    )
    (net (code "55") (name "Net-(Q3-PadG)") (class "Default")
      (node (ref "Q3") (pin "G") (pinfunction "G_G") (pintype "passive"))
      (node (ref "RG3-1") (pin "2") (pinfunction "2_2") (pintype "passive"))
      (node (ref "RG3-2") (pin "2") (pinfunction "2_2") (pintype "passive"))
    )
    (net (code "56") (name "Net-(Q4-PadG)") (class "Default")
      (node (ref "Q4") (pin "G") (pinfunction "G_G") (pintype "passive"))
      (node (ref "RG6-1") (pin "2") (pinfunction "2_2") (pintype "passive"))
      (node (ref "RG6-2") (pin "2") (pinfunction "2_2") (pintype "passive"))
    )
    (net (code "57") (name "Net-(Q5-PadG)") (class "Default")
      (node (ref "Q5") (pin "G") (pinfunction "G_G") (pintype "passive"))
      (node (ref "RG7-1") (pin "2") (pinfunction "2_2") (pintype "passive"))
      (node (ref "RG7-2") (pin "2") (pinfunction "2_2") (pintype "passive"))
    )
    (net (code "58") (name "Net-(Q6-PadG)") (class "Default")
      (node (ref "Q6") (pin "G") (pinfunction "G_G") (pintype "passive"))
      (node (ref "RG8-1") (pin "2") (pinfunction "2_2") (pintype "passive"))
      (node (ref "RG8-2") (pin "2") (pinfunction "2_2") (pintype "passive"))
    )
    (net (code "59") (name "unconnected-(JP_MC-Pad1)") (class "Default")
      (node (ref "JP_MC") (pin "1") (pinfunction "1_1") (pintype "passive"))
    )
    (net (code "60") (name "unconnected-(JP_MC-Pad3)") (class "Default")
      (node (ref "JP_MC") (pin "3") (pinfunction "3_3") (pintype "passive"))
    )
    (net (code "61") (name "unconnected-(JP_MC-Pad5)") (class "Default")
      (node (ref "JP_MC") (pin "5") (pinfunction "5_5") (pintype "passive"))
    )
    (net (code "62") (name "unconnected-(JP_MC-Pad7)") (class "Default")
      (node (ref "JP_MC") (pin "7") (pinfunction "7_7") (pintype "passive"))
    )
    (net (code "63") (name "unconnected-(JP_MC-Pad9)") (class "Default")
      (node (ref "JP_MC") (pin "9") (pinfunction "9_9") (pintype "passive"))
    )
    (net (code "64") (name "unconnected-(JP_MC-Pad11)") (class "Default")
      (node (ref "JP_MC") (pin "11") (pinfunction "11_11") (pintype "passive"))
    )
    (net (code "65") (name "unconnected-(JP_MC-Pad13)") (class "Default")
      (node (ref "JP_MC") (pin "13") (pinfunction "13_13") (pintype "passive"))
    )
    (net (code "66") (name "unconnected-(OPTO1-VE-Pad7)") (class "Default")
      (node (ref "OPTO1") (pin "7") (pinfunction "VE_7") (pintype "passive"))
    )
    (net (code "67") (name "unconnected-(OPTO2-VE-Pad7)") (class "Default")
      (node (ref "OPTO2") (pin "7") (pinfunction "VE_7") (pintype "passive"))
    )
    (net (code "68") (name "unconnected-(OPTO3-COL-Pad5)") (class "Default")
      (node (ref "OPTO3") (pin "5") (pinfunction "COL_5") (pintype "passive"))
    )
    (net (code "69") (name "unconnected-(OPTO4-COL-Pad5)") (class "Default")
      (node (ref "OPTO4") (pin "5") (pinfunction "COL_5") (pintype "passive"))
    )
    (net (code "70") (name "unconnected-(OPTO5-COL-Pad5)") (class "Default")
      (node (ref "OPTO5") (pin "5") (pinfunction "COL_5") (pintype "passive"))
    )
    (net (code "71") (name "unconnected-(OPTO6-COL-Pad5)") (class "Default")
      (node (ref "OPTO6") (pin "5") (pinfunction "COL_5") (pintype "passive"))
    )
    (net (code "72") (name "unconnected-(OPTO7-COL-Pad5)") (class "Default")
      (node (ref "OPTO7") (pin "5") (pinfunction "COL_5") (pintype "passive"))
    )
    (net (code "73") (name "unconnected-(OPTO8-COL-Pad5)") (class "Default")
      (node (ref "OPTO8") (pin "5") (pinfunction "COL_5") (pintype "passive"))
    )
  )
)
